# OLED____2022-05-08.net
KiCad netlist of a schematic drawn in Altium Designer
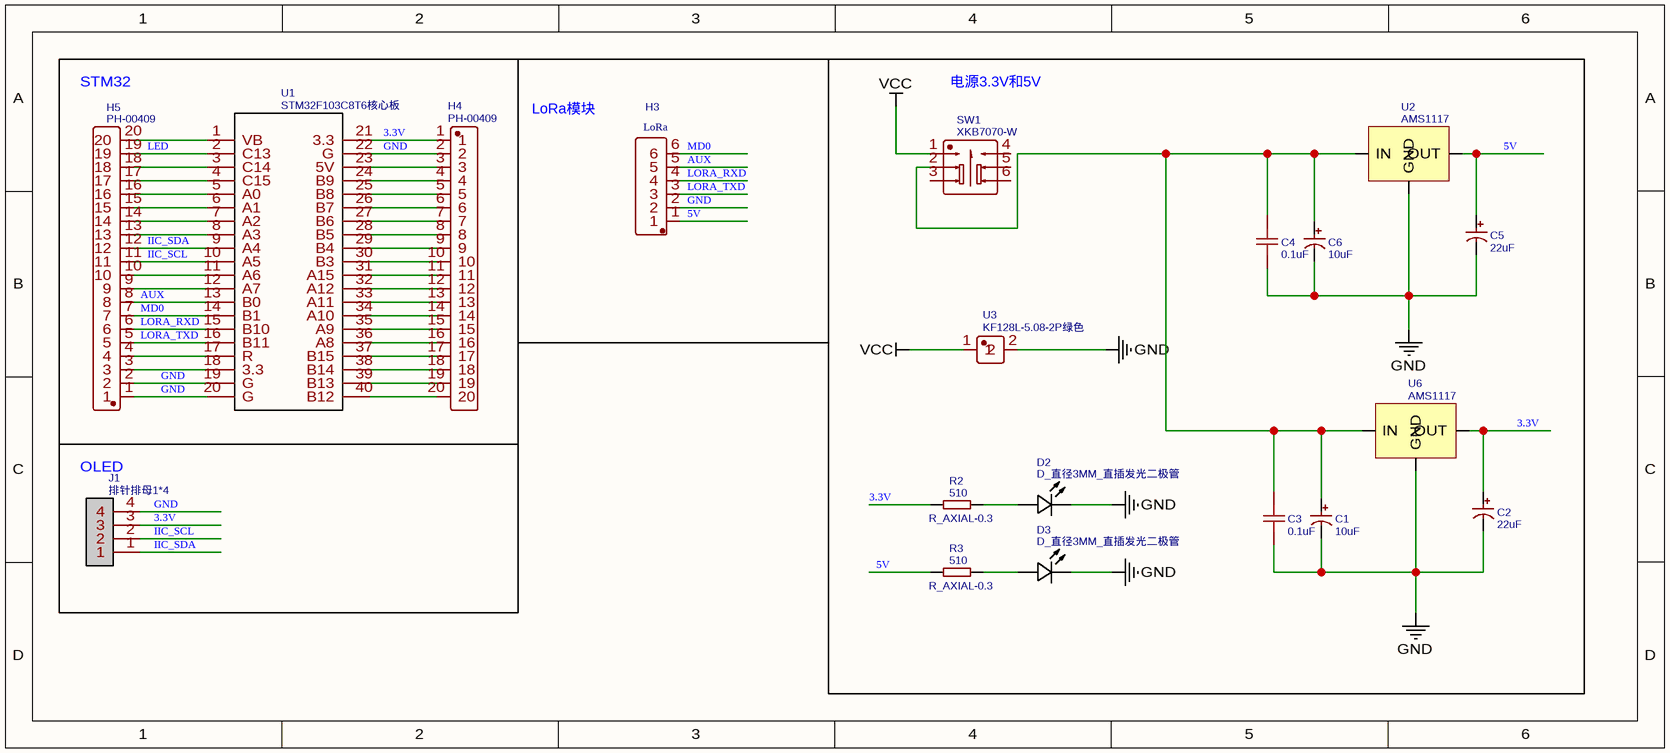
[diagram p0: OLED胸牌_从机_2022-05-08.schdoc]

(export (version "E")
  (design (tool "Eeschema 10.0.6"))
  (components
    (comp (ref "C1")
      (value "10uF")
      (fields
        (field (name "BOM_MANUFACTURER PART") "10uF 16V 3*5")
        (field (name "BOM_SUPPLIER PART") "C43798")
      )
      (libsource (lib "altium-import") (part "root_3_10uF_"))
    )
    (comp (ref "C2")
      (value "22uF")
      (fields
        (field (name "BOM_MANUFACTURER PART") "22uF 16V 4*5")
        (field (name "BOM_SUPPLIER PART") "C43800")
      )
      (libsource (lib "altium-import") (part "root_3_22uF_"))
    )
    (comp (ref "C3")
      (value "0.1uF")
      (fields
        (field (name "BOM_MANUFACTURER PART") "0603B104K500")
        (field (name "BOM_SUPPLIER PART") "C90807")
      )
      (libsource (lib "altium-import") (part "root_1_0.1uF_"))
    )
    (comp (ref "C4")
      (value "0.1uF")
      (fields
        (field (name "BOM_MANUFACTURER PART") "0603B104K500")
        (field (name "BOM_SUPPLIER PART") "C90807")
      )
      (libsource (lib "altium-import") (part "root_1_0.1uF_"))
    )
    (comp (ref "C5")
      (value "22uF")
      (fields
        (field (name "BOM_MANUFACTURER PART") "22uF 16V 4*5")
        (field (name "BOM_SUPPLIER PART") "C43800")
      )
      (libsource (lib "altium-import") (part "root_3_22uF_"))
    )
    (comp (ref "C6")
      (value "10uF")
      (fields
        (field (name "BOM_MANUFACTURER PART") "10uF 16V 3*5")
        (field (name "BOM_SUPPLIER PART") "C43798")
      )
      (libsource (lib "altium-import") (part "root_3_10uF_"))
    )
    (comp (ref "D2")
      (value "D_直径3MM_直插发光二极管")
      (fields (field (name "CONTRIBUTOR") "Jonejen"))
      (libsource (lib "altium-import") (part "root_1_D_直径3MM_直插发光二极管_"))
    )
    (comp (ref "D3")
      (value "D_直径3MM_直插发光二极管")
      (fields (field (name "CONTRIBUTOR") "Jonejen"))
      (libsource (lib "altium-import") (part "root_1_D_直径3MM_直插发光二极管_"))
    )
    (comp (ref "H3")
      (value "LoRa")
      (fields
        (field (name "BOM_MANUFACTURER PART") "220S-1*6P H=8.5MM Ytype Gold-plated")
        (field (name "BOM_SUPPLIER PART") "C124415")
        (field (name "CONTRIBUTOR") "LCSC")
      )
      (libsource (lib "altium-import") (part "root_2_LoRa_"))
    )
    (comp (ref "H4")
      (value "PH-00409")
      (fields (field (name "BOM_SUPPLIER PART") "C2685159") (field (name "CONTRIBUTOR") "LCSC"))
      (libsource (lib "altium-import") (part "root_0_PH-00409_"))
    )
    (comp (ref "H5")
      (value "PH-00409")
      (fields (field (name "BOM_SUPPLIER PART") "C2685159") (field (name "CONTRIBUTOR") "LCSC"))
      (libsource (lib "altium-import") (part "root_2_PH-00409_"))
    )
    (comp (ref "J1")
      (value "排针排母1*4")
      (fields (field (name "CONTRIBUTOR") "Li...JinHong"))
      (libsource (lib "altium-import") (part "root_2_排针排母1*4_"))
    )
    (comp (ref "R2")
      (value "510")
      (fields
        (field (name "BOM_SUPPLIER PART") "C349179")
        (field (name "BOM_MANUFACTURER PART") "ECSF2512FR050K9")
        (field (name "CONTRIBUTOR") "CYZ139")
      )
      (libsource (lib "altium-import") (part "root_0_510_"))
    )
    (comp (ref "R3")
      (value "510")
      (fields
        (field (name "BOM_SUPPLIER PART") "C349179")
        (field (name "BOM_MANUFACTURER PART") "ECSF2512FR050K9")
        (field (name "CONTRIBUTOR") "CYZ139")
      )
      (libsource (lib "altium-import") (part "root_0_510_"))
    )
    (comp (ref "SW1")
      (value "XKB7070-W")
      (fields (field (name "BOM_SUPPLIER PART") "C318864") (field (name "CONTRIBUTOR") "LCSC"))
      (libsource (lib "altium-import") (part "root_0_XKB7070-W_"))
    )
    (comp (ref "U1")
      (value "STM32F103C8T6核心板")
      (fields (field (name "CONTRIBUTOR") "yuleiweiheluo"))
      (libsource (lib "altium-import") (part "root_0_STM32F103C8T6核心板_"))
    )
    (comp (ref "U2")
      (value "AMS1117")
      (fields (field (name "CONTRIBUTOR") "zhangxiaobudong"))
      (libsource (lib "altium-import") (part "root_0_AMS1117_"))
    )
    (comp (ref "U3")
      (value "KF128L-5.08-2P绿色")
      (fields (field (name "BOM_SUPPLIER PART") "C2916952") (field (name "CONTRIBUTOR") "LCSC"))
      (libsource (lib "altium-import") (part "root_0_KF128L-5.08-2P绿色_"))
    )
    (comp (ref "U6")
      (value "AMS1117")
      (fields (field (name "CONTRIBUTOR") "zhangxiaobudong"))
      (libsource (lib "altium-import") (part "root_0_AMS1117_"))
    )
  )
  (nets
    (net (code "1") (name "/3.3V") (class "Default")
      (node (ref "C2") (pin "1") (pinfunction "1_1") (pintype "passive"))
      (node (ref "H4") (pin "1") (pinfunction "1_1") (pintype "passive"))
      (node (ref "J1") (pin "3") (pinfunction "3_3") (pintype "passive"))
      (node (ref "R2") (pin "1") (pinfunction "1_1") (pintype "passive"))
      (node (ref "U1") (pin "21") (pinfunction "3.3_21") (pintype "passive"))
      (node (ref "U6") (pin "2") (pinfunction "OUT_2") (pintype "passive"))
    )
    (net (code "2") (name "/5V") (class "Default")
      (node (ref "C5") (pin "1") (pinfunction "1_1") (pintype "passive"))
      (node (ref "H3") (pin "1") (pinfunction "1_1") (pintype "passive"))
      (node (ref "R3") (pin "1") (pinfunction "1_1") (pintype "passive"))
      (node (ref "U2") (pin "2") (pinfunction "OUT_2") (pintype "passive"))
    )
    (net (code "3") (name "/AUX") (class "Default")
      (node (ref "H3") (pin "5") (pinfunction "5_5") (pintype "passive"))
      (node (ref "H5") (pin "8") (pinfunction "8_8") (pintype "passive"))
      (node (ref "U1") (pin "13") (pinfunction "B0_13") (pintype "passive"))
    )
    (net (code "4") (name "/IIC_SCL") (class "Default")
      (node (ref "H5") (pin "11") (pinfunction "11_11") (pintype "passive"))
      (node (ref "J1") (pin "2") (pinfunction "2_2") (pintype "passive"))
      (node (ref "U1") (pin "10") (pinfunction "A5_10") (pintype "passive"))
    )
    (net (code "5") (name "/IIC_SDA") (class "Default")
      (node (ref "H5") (pin "12") (pinfunction "12_12") (pintype "passive"))
      (node (ref "J1") (pin "1") (pinfunction "1_1") (pintype "passive"))
      (node (ref "U1") (pin "9") (pinfunction "A4_9") (pintype "passive"))
    )
    (net (code "6") (name "/LED") (class "Default")
      (node (ref "H5") (pin "19") (pinfunction "19_19") (pintype "passive"))
      (node (ref "U1") (pin "2") (pinfunction "C13_2") (pintype "passive"))
    )
    (net (code "7") (name "/LORA_RXD") (class "Default")
      (node (ref "H3") (pin "4") (pinfunction "4_4") (pintype "passive"))
      (node (ref "H5") (pin "6") (pinfunction "6_6") (pintype "passive"))
      (node (ref "U1") (pin "15") (pinfunction "B10_15") (pintype "passive"))
    )
    (net (code "8") (name "/LORA_TXD") (class "Default")
      (node (ref "H3") (pin "3") (pinfunction "3_3") (pintype "passive"))
      (node (ref "H5") (pin "5") (pinfunction "5_5") (pintype "passive"))
      (node (ref "U1") (pin "16") (pinfunction "B11_16") (pintype "passive"))
    )
    (net (code "9") (name "/MD0") (class "Default")
      (node (ref "H3") (pin "6") (pinfunction "6_6") (pintype "passive"))
      (node (ref "H5") (pin "7") (pinfunction "7_7") (pintype "passive"))
      (node (ref "U1") (pin "14") (pinfunction "B1_14") (pintype "passive"))
    )
    (net (code "10") (name "GND") (class "Default")
      (node (ref "C1") (pin "2") (pinfunction "2_2") (pintype "passive"))
      (node (ref "C2") (pin "2") (pinfunction "2_2") (pintype "passive"))
      (node (ref "C3") (pin "1") (pinfunction "1_1") (pintype "passive"))
      (node (ref "C4") (pin "1") (pinfunction "1_1") (pintype "passive"))
      (node (ref "C5") (pin "2") (pinfunction "2_2") (pintype "passive"))
      (node (ref "C6") (pin "2") (pinfunction "2_2") (pintype "passive"))
      (node (ref "D2") (pin "2") (pinfunction "K_2") (pintype "passive"))
      (node (ref "D3") (pin "2") (pinfunction "K_2") (pintype "passive"))
      (node (ref "H3") (pin "2") (pinfunction "2_2") (pintype "passive"))
      (node (ref "H4") (pin "2") (pinfunction "2_2") (pintype "passive"))
      (node (ref "H5") (pin "1") (pinfunction "1_1") (pintype "passive"))
      (node (ref "H5") (pin "2") (pinfunction "2_2") (pintype "passive"))
      (node (ref "J1") (pin "4") (pinfunction "4_4") (pintype "passive"))
      (node (ref "U1") (pin "19") (pinfunction "G_19") (pintype "passive"))
      (node (ref "U1") (pin "20") (pinfunction "G_20") (pintype "passive"))
      (node (ref "U1") (pin "22") (pinfunction "G_22") (pintype "passive"))
      (node (ref "U2") (pin "1") (pinfunction "GND_1") (pintype "passive"))
      (node (ref "U3") (pin "2") (pinfunction "2_2") (pintype "passive"))
      (node (ref "U6") (pin "1") (pinfunction "GND_1") (pintype "passive"))
    )
    (net (code "11") (name "Net-(D2-A)") (class "Default")
      (node (ref "D2") (pin "1") (pinfunction "A_1") (pintype "passive"))
      (node (ref "R2") (pin "2") (pinfunction "2_2") (pintype "passive"))
    )
    (net (code "12") (name "Net-(D3-A)") (class "Default")
      (node (ref "D3") (pin "1") (pinfunction "A_1") (pintype "passive"))
      (node (ref "R3") (pin "2") (pinfunction "2_2") (pintype "passive"))
    )
    (net (code "13") (name "Net-(H5-Pad3)") (class "Default")
      (node (ref "H5") (pin "3") (pinfunction "3_3") (pintype "passive"))
      (node (ref "U1") (pin "18") (pinfunction "3.3_18") (pintype "passive"))
    )
    (net (code "14") (name "Net-(U1-5V)") (class "Default")
      (node (ref "H4") (pin "3") (pinfunction "3_3") (pintype "passive"))
      (node (ref "U1") (pin "23") (pinfunction "5V_23") (pintype "passive"))
    )
    (net (code "15") (name "Net-(U1-A0)") (class "Default")
      (node (ref "H5") (pin "16") (pinfunction "16_16") (pintype "passive"))
      (node (ref "U1") (pin "5") (pinfunction "A0_5") (pintype "passive"))
    )
    (net (code "16") (name "Net-(U1-A1)") (class "Default")
      (node (ref "H5") (pin "15") (pinfunction "15_15") (pintype "passive"))
      (node (ref "U1") (pin "6") (pinfunction "A1_6") (pintype "passive"))
    )
    (net (code "17") (name "Net-(U1-A2)") (class "Default")
      (node (ref "H5") (pin "14") (pinfunction "14_14") (pintype "passive"))
      (node (ref "U1") (pin "7") (pinfunction "A2_7") (pintype "passive"))
    )
    (net (code "18") (name "Net-(U1-A3)") (class "Default")
      (node (ref "H5") (pin "13") (pinfunction "13_13") (pintype "passive"))
      (node (ref "U1") (pin "8") (pinfunction "A3_8") (pintype "passive"))
    )
    (net (code "19") (name "Net-(U1-A6)") (class "Default")
      (node (ref "H5") (pin "10") (pinfunction "10_10") (pintype "passive"))
      (node (ref "U1") (pin "11") (pinfunction "A6_11") (pintype "passive"))
    )
    (net (code "20") (name "Net-(U1-A7)") (class "Default")
      (node (ref "H5") (pin "9") (pinfunction "9_9") (pintype "passive"))
      (node (ref "U1") (pin "12") (pinfunction "A7_12") (pintype "passive"))
    )
    (net (code "21") (name "Net-(U1-A8)") (class "Default")
      (node (ref "H4") (pin "16") (pinfunction "16_16") (pintype "passive"))
      (node (ref "U1") (pin "36") (pinfunction "A8_36") (pintype "passive"))
    )
    (net (code "22") (name "Net-(U1-A9)") (class "Default")
      (node (ref "H4") (pin "15") (pinfunction "15_15") (pintype "passive"))
      (node (ref "U1") (pin "35") (pinfunction "A9_35") (pintype "passive"))
    )
    (net (code "23") (name "Net-(U1-A10)") (class "Default")
      (node (ref "H4") (pin "14") (pinfunction "14_14") (pintype "passive"))
      (node (ref "U1") (pin "34") (pinfunction "A10_34") (pintype "passive"))
    )
    (net (code "24") (name "Net-(U1-A11)") (class "Default")
      (node (ref "H4") (pin "13") (pinfunction "13_13") (pintype "passive"))
      (node (ref "U1") (pin "33") (pinfunction "A11_33") (pintype "passive"))
    )
    (net (code "25") (name "Net-(U1-A12)") (class "Default")
      (node (ref "H4") (pin "12") (pinfunction "12_12") (pintype "passive"))
      (node (ref "U1") (pin "32") (pinfunction "A12_32") (pintype "passive"))
    )
    (net (code "26") (name "Net-(U1-A15)") (class "Default")
      (node (ref "H4") (pin "11") (pinfunction "11_11") (pintype "passive"))
      (node (ref "U1") (pin "31") (pinfunction "A15_31") (pintype "passive"))
    )
    (net (code "27") (name "Net-(U1-B3)") (class "Default")
      (node (ref "H4") (pin "10") (pinfunction "10_10") (pintype "passive"))
      (node (ref "U1") (pin "30") (pinfunction "B3_30") (pintype "passive"))
    )
    (net (code "28") (name "Net-(U1-B4)") (class "Default")
      (node (ref "H4") (pin "9") (pinfunction "9_9") (pintype "passive"))
      (node (ref "U1") (pin "29") (pinfunction "B4_29") (pintype "passive"))
    )
    (net (code "29") (name "Net-(U1-B5)") (class "Default")
      (node (ref "H4") (pin "8") (pinfunction "8_8") (pintype "passive"))
      (node (ref "U1") (pin "28") (pinfunction "B5_28") (pintype "passive"))
    )
    (net (code "30") (name "Net-(U1-B6)") (class "Default")
      (node (ref "H4") (pin "7") (pinfunction "7_7") (pintype "passive"))
      (node (ref "U1") (pin "27") (pinfunction "B6_27") (pintype "passive"))
    )
    (net (code "31") (name "Net-(U1-B7)") (class "Default")
      (node (ref "H4") (pin "6") (pinfunction "6_6") (pintype "passive"))
      (node (ref "U1") (pin "26") (pinfunction "B7_26") (pintype "passive"))
    )
    (net (code "32") (name "Net-(U1-B8)") (class "Default")
      (node (ref "H4") (pin "5") (pinfunction "5_5") (pintype "passive"))
      (node (ref "U1") (pin "25") (pinfunction "B8_25") (pintype "passive"))
    )
    (net (code "33") (name "Net-(U1-B9)") (class "Default")
      (node (ref "H4") (pin "4") (pinfunction "4_4") (pintype "passive"))
      (node (ref "U1") (pin "24") (pinfunction "B9_24") (pintype "passive"))
    )
    (net (code "34") (name "Net-(U1-B12)") (class "Default")
      (node (ref "H4") (pin "20") (pinfunction "20_20") (pintype "passive"))
      (node (ref "U1") (pin "40") (pinfunction "B12_40") (pintype "passive"))
    )
    (net (code "35") (name "Net-(U1-B13)") (class "Default")
      (node (ref "H4") (pin "19") (pinfunction "19_19") (pintype "passive"))
      (node (ref "U1") (pin "39") (pinfunction "B13_39") (pintype "passive"))
    )
    (net (code "36") (name "Net-(U1-B14)") (class "Default")
      (node (ref "H4") (pin "18") (pinfunction "18_18") (pintype "passive"))
      (node (ref "U1") (pin "38") (pinfunction "B14_38") (pintype "passive"))
    )
    (net (code "37") (name "Net-(U1-B15)") (class "Default")
      (node (ref "H4") (pin "17") (pinfunction "17_17") (pintype "passive"))
      (node (ref "U1") (pin "37") (pinfunction "B15_37") (pintype "passive"))
    )
    (net (code "38") (name "Net-(U1-C14)") (class "Default")
      (node (ref "H5") (pin "18") (pinfunction "18_18") (pintype "passive"))
      (node (ref "U1") (pin "3") (pinfunction "C14_3") (pintype "passive"))
    )
    (net (code "39") (name "Net-(U1-C15)") (class "Default")
      (node (ref "H5") (pin "17") (pinfunction "17_17") (pintype "passive"))
      (node (ref "U1") (pin "4") (pinfunction "C15_4") (pintype "passive"))
    )
    (net (code "40") (name "Net-(U1-R)") (class "Default")
      (node (ref "H5") (pin "4") (pinfunction "4_4") (pintype "passive"))
      (node (ref "U1") (pin "17") (pinfunction "R_17") (pintype "passive"))
    )
    (net (code "41") (name "Net-(U1-VB)") (class "Default")
      (node (ref "H5") (pin "20") (pinfunction "20_20") (pintype "passive"))
      (node (ref "U1") (pin "1") (pinfunction "VB_1") (pintype "passive"))
    )
    (net (code "42") (name "Net-(U2-IN)") (class "Default")
      (node (ref "C1") (pin "1") (pinfunction "1_1") (pintype "passive"))
      (node (ref "C3") (pin "2") (pinfunction "2_2") (pintype "passive"))
      (node (ref "C4") (pin "2") (pinfunction "2_2") (pintype "passive"))
      (node (ref "C6") (pin "1") (pinfunction "1_1") (pintype "passive"))
      (node (ref "SW1") (pin "2") (pinfunction "2_2") (pintype "passive"))
      (node (ref "U2") (pin "3") (pinfunction "IN_3") (pintype "passive"))
      (node (ref "U6") (pin "3") (pinfunction "IN_3") (pintype "passive"))
    )
    (net (code "43") (name "VCC") (class "Default")
      (node (ref "SW1") (pin "1") (pinfunction "1_1") (pintype "passive"))
      (node (ref "U3") (pin "1") (pinfunction "1_1") (pintype "passive"))
    )
    (net (code "44") (name "unconnected-(SW1-Pad3)") (class "Default")
      (node (ref "SW1") (pin "3") (pinfunction "3_3") (pintype "passive"))
    )
    (net (code "45") (name "unconnected-(SW1-Pad4)") (class "Default")
      (node (ref "SW1") (pin "4") (pinfunction "4_4") (pintype "passive"))
    )
    (net (code "46") (name "unconnected-(SW1-Pad5)") (class "Default")
      (node (ref "SW1") (pin "5") (pinfunction "5_5") (pintype "passive"))
    )
    (net (code "47") (name "unconnected-(SW1-Pad6)") (class "Default")
      (node (ref "SW1") (pin "6") (pinfunction "6_6") (pintype "passive"))
    )
  )
)
